# IMU.net
KiCad netlist of a schematic drawn in Altium Designer
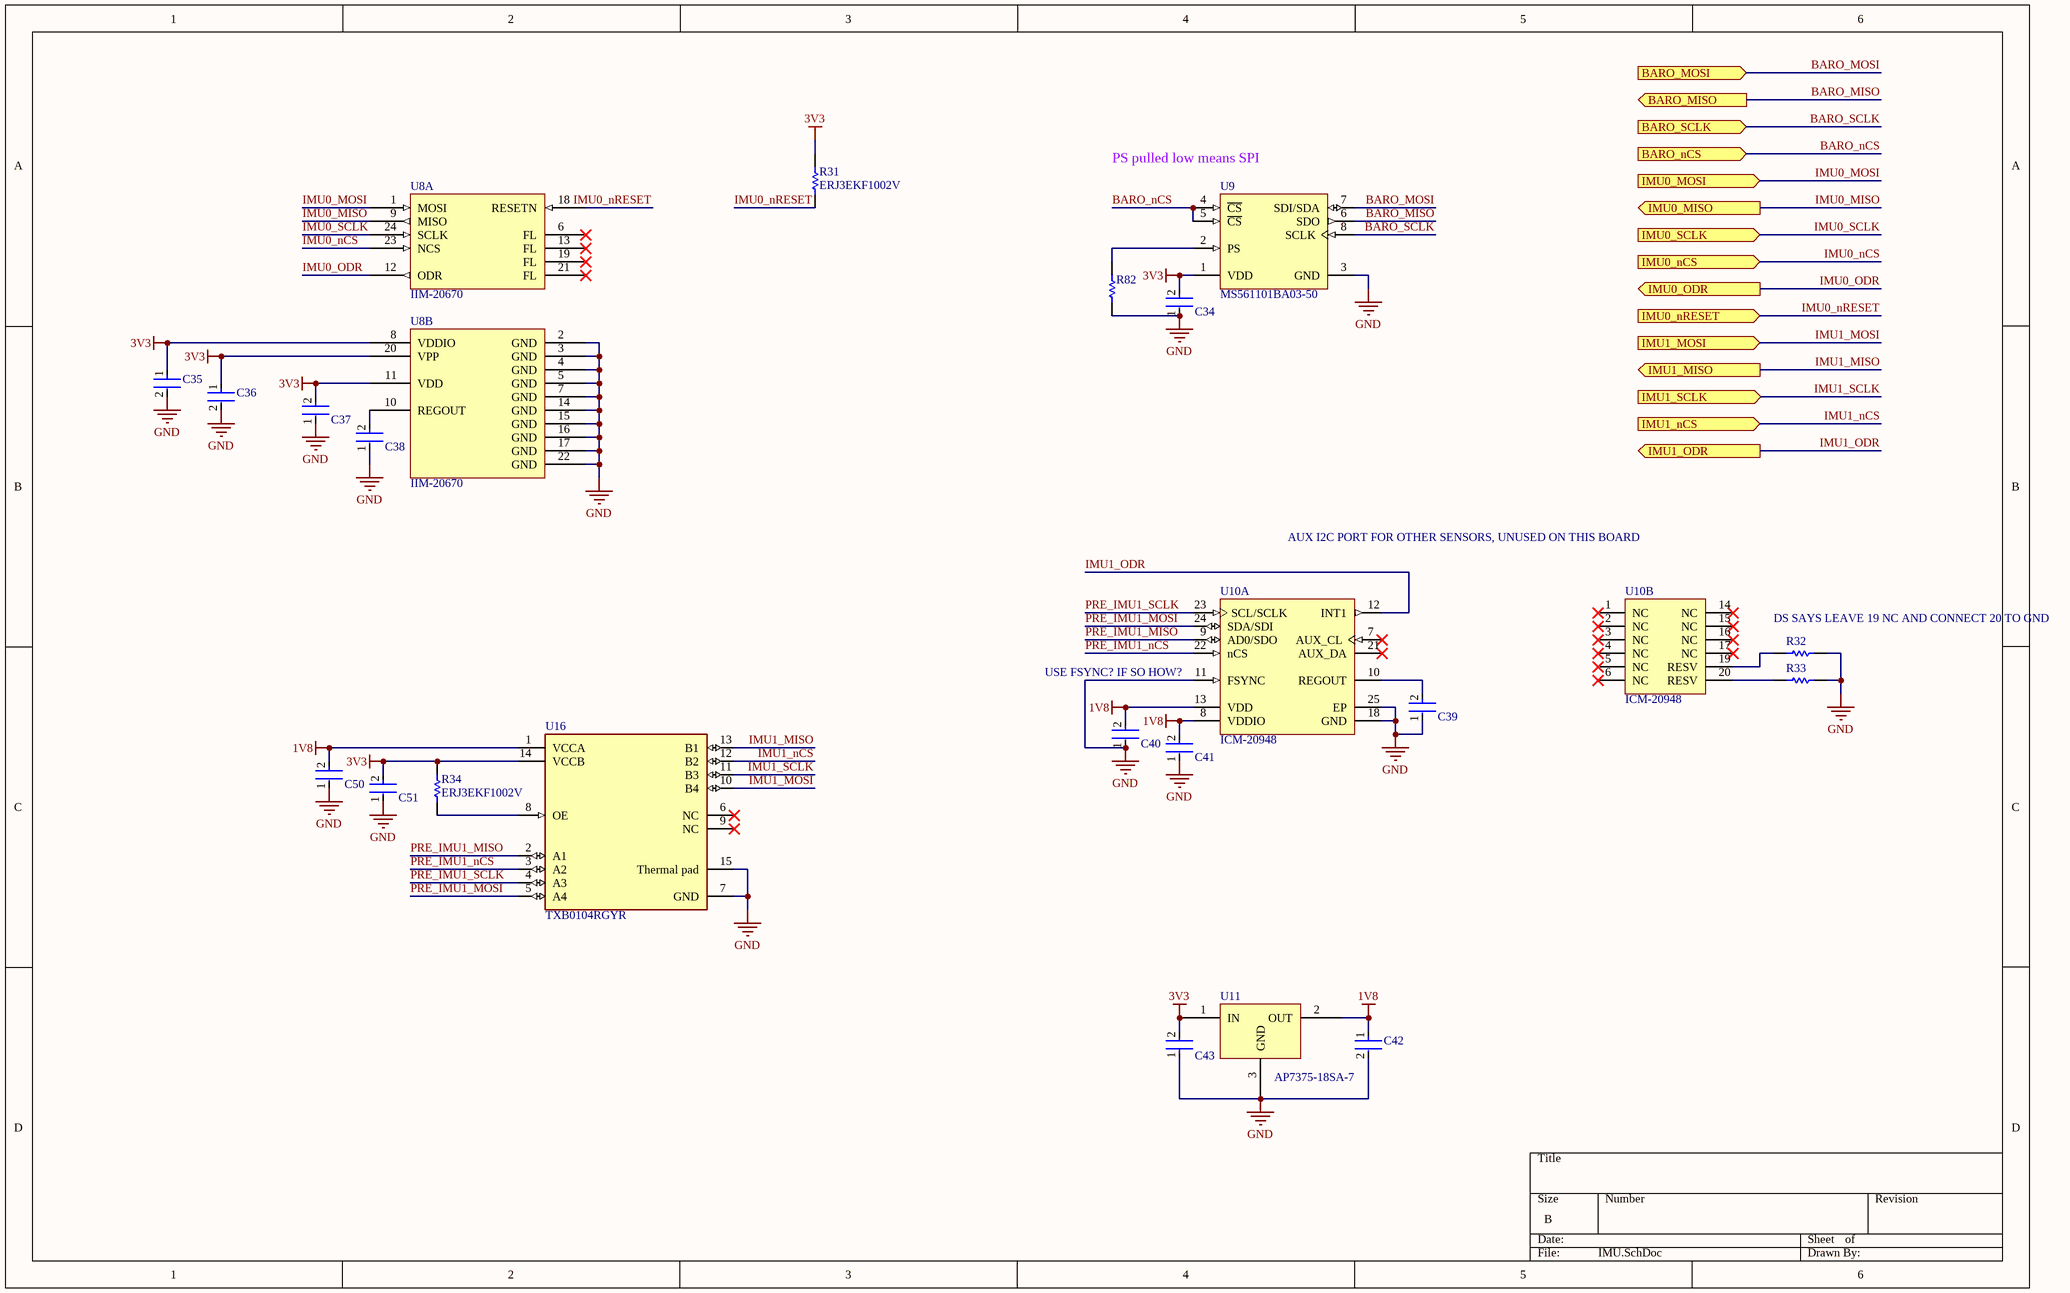
[diagram p0: IMU.SchDoc]

(export (version "E")
  (design (tool "Eeschema 10.0.6"))
  (components
    (comp (ref "C34")
      (value "GRM155R71C104KA88D")
      (footprint "FP-GRM15-MFG")
      (description "CAP CER 0.1UF 16V X7R 0402")
      (fields
        (field (name "TOLERANCE") "10%")
        (field (name "OCTOPART") "https://octopart.com/grm155r71c104ka88d-murata-196880")
      )
      (libsource (lib "Altium Content Vault") (part "236180d848d6139a670b325ea6854c9"))
    )
    (comp (ref "C35")
      (value "CC0402KPX7R7BB103")
      (footprint "FP-CC0402-MFG")
      (description "CC0402 10 nF X7R 10.00% 16 V")
      (fields
        (field (name "TOLERANCE") "0.1")
        (field (name "OCTOPART") "https://octopart.com/cc0402kpx7r7bb103-yageo-12885102")
      )
      (libsource (lib "Altium Content Vault") (part "11868f565c42a9108669ba33697ecf6"))
    )
    (comp (ref "C36")
      (value "CC0402KPX7R7BB103")
      (footprint "FP-CC0402-MFG")
      (description "CC0402 10 nF X7R 10.00% 16 V")
      (fields
        (field (name "TOLERANCE") "0.1")
        (field (name "OCTOPART") "https://octopart.com/cc0402kpx7r7bb103-yageo-12885102")
      )
      (libsource (lib "Altium Content Vault") (part "11868f565c42a9108669ba33697ecf6"))
    )
    (comp (ref "C37")
      (value "GRM155R71C104KA88D")
      (footprint "FP-GRM15-MFG")
      (description "CAP CER 0.1UF 16V X7R 0402")
      (fields
        (field (name "TOLERANCE") "10%")
        (field (name "OCTOPART") "https://octopart.com/grm155r71c104ka88d-murata-196880")
      )
      (libsource (lib "Altium Content Vault") (part "236180d848d6139a670b325ea6854c9"))
    )
    (comp (ref "C38")
      (value "GRM155R71C104KA88D")
      (footprint "FP-GRM15-MFG")
      (description "CAP CER 0.1UF 16V X7R 0402")
      (fields
        (field (name "TOLERANCE") "10%")
        (field (name "OCTOPART") "https://octopart.com/grm155r71c104ka88d-murata-196880")
      )
      (libsource (lib "Altium Content Vault") (part "236180d848d6139a670b325ea6854c9"))
    )
    (comp (ref "C39")
      (value "GRM155R71C104KA88D")
      (footprint "FP-GRM15-MFG")
      (description "CAP CER 0.1UF 16V X7R 0402")
      (fields
        (field (name "TOLERANCE") "10%")
        (field (name "OCTOPART") "https://octopart.com/grm155r71c104ka88d-murata-196880")
      )
      (libsource (lib "Altium Content Vault") (part "236180d848d6139a670b325ea6854c9"))
    )
    (comp (ref "C40")
      (value "GRM155R71C104KA88D")
      (footprint "FP-GRM15-MFG")
      (description "CAP CER 0.1UF 16V X7R 0402")
      (fields
        (field (name "TOLERANCE") "10%")
        (field (name "OCTOPART") "https://octopart.com/grm155r71c104ka88d-murata-196880")
      )
      (libsource (lib "Altium Content Vault") (part "236180d848d6139a670b325ea6854c9"))
    )
    (comp (ref "C41")
      (value "GRM155R71C104KA88D")
      (footprint "FP-GRM15-MFG")
      (description "CAP CER 0.1UF 16V X7R 0402")
      (fields
        (field (name "TOLERANCE") "10%")
        (field (name "OCTOPART") "https://octopart.com/grm155r71c104ka88d-murata-196880")
      )
      (libsource (lib "Altium Content Vault") (part "236180d848d6139a670b325ea6854c9"))
    )
    (comp (ref "C42")
      (value "CL05A106MP5NUNC")
      (footprint "FP-CL05A106MP5NUNC-MFG")
      (description "CAP CER 10UF 10V X5R 0402")
      (fields
        (field (name "OCTOPART") "https://octopart.com/cl05a106mp5nunc-samsung-22457395")
        (field (name "TOLERANCE") "20%")
      )
      (libsource (lib "Altium Content Vault") (part "b4654b650e69147ec39a6b967a45e02"))
    )
    (comp (ref "C43")
      (value "C0402C104K8PACTU")
      (footprint "FP-C0402-BB-MFG")
      (description "CAP CER 0.1UF 10V X5R 0402")
      (fields (field (name "MANUFACTURER") "Kemet") (field (name "TOLERANCE") "0.1"))
      (libsource (lib "Altium Content Vault") (part "b4654b650e69147ec39a6b967a45e02"))
    )
    (comp (ref "C50")
      (value "GRM155R71C104KA88D")
      (footprint "FP-GRM15-MFG")
      (description "CAP CER 0.1UF 16V X7R 0402")
      (fields
        (field (name "TOLERANCE") "10%")
        (field (name "OCTOPART") "https://octopart.com/grm155r71c104ka88d-murata-196880")
      )
      (libsource (lib "Altium Content Vault") (part "236180d848d6139a670b325ea6854c9"))
    )
    (comp (ref "C51")
      (value "GRM155R71C104KA88D")
      (footprint "FP-GRM15-MFG")
      (description "CAP CER 0.1UF 16V X7R 0402")
      (fields
        (field (name "TOLERANCE") "10%")
        (field (name "OCTOPART") "https://octopart.com/grm155r71c104ka88d-murata-196880")
      )
      (libsource (lib "Altium Content Vault") (part "236180d848d6139a670b325ea6854c9"))
    )
    (comp (ref "R31")
      (value "ERJ3EKF1002V")
      (footprint "RESC1609X55X30LL15T15")
      (description "Chip Resistor, 10 KOhm, +/- 1%, 0.1 W, -55 to 155 degC, 0603 (1608 Metric), RoHS, Tape and Reel")
      (fields (field (name "TOLERANCE") "1%") (field (name "MANUFACTURER") "Panasonic"))
      (libsource (lib "Altium Content Vault") (part "RES-2"))
    )
    (comp (ref "R32")
      (value "0402 JUMPER")
      (footprint "RESC1005X40X25ML05T05")
      (description "READ THE NAME")
      (libsource (lib "Space Concordia") (part "CMP-009-00206-2"))
    )
    (comp (ref "R33")
      (value "0402 JUMPER")
      (footprint "RESC1005X40X25ML05T05")
      (description "READ THE NAME")
      (libsource (lib "Space Concordia") (part "CMP-009-00206-2"))
    )
    (comp (ref "R34")
      (value "ERJ3EKF1002V")
      (footprint "RESC1609X55X30LL15T15")
      (description "Chip Resistor, 10 KOhm, +/- 1%, 0.1 W, -55 to 155 degC, 0603 (1608 Metric), RoHS, Tape and Reel")
      (fields (field (name "TOLERANCE") "1%") (field (name "MANUFACTURER") "Panasonic"))
      (libsource (lib "Altium Content Vault") (part "RES-2"))
    )
    (comp (ref "R82")
      (value "0402 JUMPER")
      (footprint "RESC1005X40X25ML05T05")
      (description "READ THE NAME")
      (libsource (lib "Space Concordia") (part "CMP-009-00206-2"))
    )
    (comp (ref "U8")
      (value "IIM-20670")
      (footprint "PQFN50P450X450X115_HS-25N")
      (description "6-axis IMU with extended temperature range and high VRE performance")
      (libsource (lib "Space Concordia") (part "IIM-20670"))
    )
    (comp (ref "U9")
      (value "MS561101BA03-50")
      (footprint "MSI-MS561101BA03-50-8_V")
      (fields (field (name "MANUFACTURER") "Measurement Specialties"))
      (libsource (lib "Altium Content Vault") (part "MSI-MS561101BA03-50-8"))
    )
    (comp (ref "U10")
      (value "ICM-20948")
      (footprint "TDK-QFN-24_L")
      (fields (field (name "MANUFACTURER") "TDK"))
      (libsource (lib "Altium Content Vault") (part "TDK-ICM-20948-QFN-24"))
    )
    (comp (ref "U11")
      (value "AP7375-18SA-7")
      (footprint "AP7375-18SA-7-Footprint-1")
      (description "Fixed Positive LDO Regulator")
      (libsource (lib "Space Concordia") (part "AP7375-18SA-7"))
    )
    (comp (ref "U16")
      (value "TXB0104RGYR")
      (footprint "FP-RGY0014A-MFG")
      (description "IC TRNSLTR BIDIRECTIONAL 14VQFN")
      (fields
        (field (name "MANUFACTURER") "Texas Instruments")
        (field (name "OCTOPART") "https://octopart.com/txb0104rgyr-texas+instruments-1485948")
      )
      (libsource (lib "Altium Content Vault") (part "00c1e25395d90d543401131e0a6fef8"))
    )
  )
  (nets
    (net (code "1") (name "/BARO_MISO") (class "Default")
      (node (ref "U9") (pin "6") (pinfunction "SDO_6") (pintype "output"))
    )
    (net (code "2") (name "/BARO_MOSI") (class "Default")
      (node (ref "U9") (pin "7") (pinfunction "SDI/SDA_7") (pintype "bidirectional"))
    )
    (net (code "3") (name "/BARO_SCLK") (class "Default")
      (node (ref "U9") (pin "8") (pinfunction "SCLK_8") (pintype "input"))
    )
    (net (code "4") (name "/BARO_nCS") (class "Default")
      (node (ref "U9") (pin "4") (pinfunction "~{CS}_4") (pintype "input"))
      (node (ref "U9") (pin "5") (pinfunction "~{CS}_5") (pintype "input"))
    )
    (net (code "5") (name "/IMU0_MISO") (class "Default")
      (node (ref "U8") (pin "9") (pinfunction "MISO_9") (pintype "output"))
    )
    (net (code "6") (name "/IMU0_MOSI") (class "Default")
      (node (ref "U8") (pin "1") (pinfunction "MOSI_1") (pintype "input"))
    )
    (net (code "7") (name "/IMU0_ODR") (class "Default")
      (node (ref "U8") (pin "12") (pinfunction "ODR_12") (pintype "output"))
    )
    (net (code "8") (name "/IMU0_SCLK") (class "Default")
      (node (ref "U8") (pin "24") (pinfunction "SCLK_24") (pintype "input"))
    )
    (net (code "9") (name "/IMU0_nCS") (class "Default")
      (node (ref "U8") (pin "23") (pinfunction "NCS_23") (pintype "input"))
    )
    (net (code "10") (name "/IMU0_nRESET") (class "Default")
      (node (ref "R31") (pin "1") (pinfunction "1_1") (pintype "passive"))
      (node (ref "U8") (pin "18") (pinfunction "RESETN_18") (pintype "input"))
    )
    (net (code "11") (name "/IMU1_MISO") (class "Default")
      (node (ref "U16") (pin "13") (pinfunction "B1_13") (pintype "bidirectional"))
    )
    (net (code "12") (name "/IMU1_MOSI") (class "Default")
      (node (ref "U16") (pin "10") (pinfunction "B4_10") (pintype "bidirectional"))
    )
    (net (code "13") (name "/IMU1_ODR") (class "Default")
      (node (ref "U10") (pin "12") (pinfunction "INT1_12") (pintype "output"))
    )
    (net (code "14") (name "/IMU1_SCLK") (class "Default")
      (node (ref "U16") (pin "11") (pinfunction "B3_11") (pintype "bidirectional"))
    )
    (net (code "15") (name "/IMU1_nCS") (class "Default")
      (node (ref "U16") (pin "12") (pinfunction "B2_12") (pintype "bidirectional"))
    )
    (net (code "16") (name "/PRE_IMU1_MISO") (class "Default")
      (node (ref "U10") (pin "9") (pinfunction "AD0/SDO_9") (pintype "bidirectional"))
      (node (ref "U16") (pin "2") (pinfunction "A1_2") (pintype "bidirectional"))
    )
    (net (code "17") (name "/PRE_IMU1_MOSI") (class "Default")
      (node (ref "U10") (pin "24") (pinfunction "SDA/SDI_24") (pintype "bidirectional"))
      (node (ref "U16") (pin "5") (pinfunction "A4_5") (pintype "bidirectional"))
    )
    (net (code "18") (name "/PRE_IMU1_SCLK") (class "Default")
      (node (ref "U10") (pin "23") (pinfunction "SCL/SCLK_23") (pintype "input"))
      (node (ref "U16") (pin "4") (pinfunction "A3_4") (pintype "bidirectional"))
    )
    (net (code "19") (name "/PRE_IMU1_nCS") (class "Default")
      (node (ref "U10") (pin "22") (pinfunction "nCS_22") (pintype "input"))
      (node (ref "U16") (pin "3") (pinfunction "A2_3") (pintype "bidirectional"))
    )
    (net (code "20") (name "1V8") (class "Default")
      (node (ref "C40") (pin "2") (pinfunction "2_2") (pintype "passive"))
      (node (ref "C41") (pin "2") (pinfunction "2_2") (pintype "passive"))
      (node (ref "C42") (pin "1") (pinfunction "1_1") (pintype "passive"))
      (node (ref "C50") (pin "2") (pinfunction "2_2") (pintype "passive"))
      (node (ref "U10") (pin "13") (pinfunction "VDD_13") (pintype "power_in"))
      (node (ref "U10") (pin "8") (pinfunction "VDDIO_8") (pintype "power_in"))
      (node (ref "U11") (pin "2") (pinfunction "OUT_2") (pintype "passive"))
      (node (ref "U16") (pin "1") (pinfunction "VCCA_1") (pintype "power_in"))
    )
    (net (code "21") (name "3V3") (class "Default")
      (node (ref "C34") (pin "2") (pinfunction "2_2") (pintype "passive"))
      (node (ref "C35") (pin "1") (pinfunction "1_1") (pintype "passive"))
      (node (ref "C36") (pin "1") (pinfunction "1_1") (pintype "passive"))
      (node (ref "C37") (pin "2") (pinfunction "2_2") (pintype "passive"))
      (node (ref "C43") (pin "2") (pinfunction "2_2") (pintype "passive"))
      (node (ref "C51") (pin "2") (pinfunction "2_2") (pintype "passive"))
      (node (ref "R31") (pin "2") (pinfunction "2_2") (pintype "passive"))
      (node (ref "R34") (pin "2") (pinfunction "2_2") (pintype "passive"))
      (node (ref "U11") (pin "1") (pinfunction "IN_1") (pintype "passive"))
      (node (ref "U16") (pin "14") (pinfunction "VCCB_14") (pintype "power_in"))
      (node (ref "U8") (pin "11") (pinfunction "VDD_11") (pintype "power_in"))
      (node (ref "U8") (pin "20") (pinfunction "VPP_20") (pintype "power_in"))
      (node (ref "U8") (pin "8") (pinfunction "VDDIO_8") (pintype "power_in"))
      (node (ref "U9") (pin "1") (pinfunction "VDD_1") (pintype "power_in"))
    )
    (net (code "22") (name "GND") (class "Default")
      (node (ref "C34") (pin "1") (pinfunction "1_1") (pintype "passive"))
      (node (ref "C35") (pin "2") (pinfunction "2_2") (pintype "passive"))
      (node (ref "C36") (pin "2") (pinfunction "2_2") (pintype "passive"))
      (node (ref "C37") (pin "1") (pinfunction "1_1") (pintype "passive"))
      (node (ref "C38") (pin "1") (pinfunction "1_1") (pintype "passive"))
      (node (ref "C39") (pin "1") (pinfunction "1_1") (pintype "passive"))
      (node (ref "C40") (pin "1") (pinfunction "1_1") (pintype "passive"))
      (node (ref "C41") (pin "1") (pinfunction "1_1") (pintype "passive"))
      (node (ref "C42") (pin "2") (pinfunction "2_2") (pintype "passive"))
      (node (ref "C43") (pin "1") (pinfunction "1_1") (pintype "passive"))
      (node (ref "C50") (pin "1") (pinfunction "1_1") (pintype "passive"))
      (node (ref "C51") (pin "1") (pinfunction "1_1") (pintype "passive"))
      (node (ref "R32") (pin "2") (pinfunction "2_2") (pintype "passive"))
      (node (ref "R33") (pin "2") (pinfunction "2_2") (pintype "passive"))
      (node (ref "R82") (pin "1") (pinfunction "1_1") (pintype "passive"))
      (node (ref "U10") (pin "11") (pinfunction "FSYNC_11") (pintype "input"))
      (node (ref "U10") (pin "18") (pinfunction "GND_18") (pintype "power_in"))
      (node (ref "U10") (pin "25") (pinfunction "EP_25") (pintype "passive"))
      (node (ref "U11") (pin "3") (pinfunction "GND_3") (pintype "passive"))
      (node (ref "U16") (pin "15") (pinfunction "Thermal_pad_15") (pintype "power_in"))
      (node (ref "U16") (pin "7") (pinfunction "GND_7") (pintype "power_in"))
      (node (ref "U8") (pin "14") (pinfunction "GND_14") (pintype "power_in"))
      (node (ref "U8") (pin "15") (pinfunction "GND_15") (pintype "power_in"))
      (node (ref "U8") (pin "16") (pinfunction "GND_16") (pintype "power_in"))
      (node (ref "U8") (pin "17") (pinfunction "GND_17") (pintype "power_in"))
      (node (ref "U8") (pin "2") (pinfunction "GND_2") (pintype "power_in"))
      (node (ref "U8") (pin "22") (pinfunction "GND_22") (pintype "power_in"))
      (node (ref "U8") (pin "3") (pinfunction "GND_3") (pintype "power_in"))
      (node (ref "U8") (pin "4") (pinfunction "GND_4") (pintype "power_in"))
      (node (ref "U8") (pin "5") (pinfunction "GND_5") (pintype "power_in"))
      (node (ref "U8") (pin "7") (pinfunction "GND_7") (pintype "power_in"))
      (node (ref "U9") (pin "3") (pinfunction "GND_3") (pintype "power_in"))
    )
    (net (code "23") (name "Net-(R32-Pad1)") (class "Default")
      (node (ref "R32") (pin "1") (pinfunction "1_1") (pintype "passive"))
      (node (ref "U10") (pin "19") (pinfunction "RESV_19") (pintype "passive"))
    )
    (net (code "24") (name "Net-(R33-Pad1)") (class "Default")
      (node (ref "R33") (pin "1") (pinfunction "1_1") (pintype "passive"))
      (node (ref "U10") (pin "20") (pinfunction "RESV_20") (pintype "passive"))
    )
    (net (code "25") (name "Net-(U8B-REGOUT)") (class "Default")
      (node (ref "C38") (pin "2") (pinfunction "2_2") (pintype "passive"))
      (node (ref "U8") (pin "10") (pinfunction "REGOUT_10") (pintype "passive"))
    )
    (net (code "26") (name "Net-(U9-PS)") (class "Default")
      (node (ref "R82") (pin "2") (pinfunction "2_2") (pintype "passive"))
      (node (ref "U9") (pin "2") (pinfunction "PS_2") (pintype "input"))
    )
    (net (code "27") (name "Net-(U10A-REGOUT)") (class "Default")
      (node (ref "C39") (pin "2") (pinfunction "2_2") (pintype "passive"))
      (node (ref "U10") (pin "10") (pinfunction "REGOUT_10") (pintype "passive"))
    )
    (net (code "28") (name "Net-(U16-OE)") (class "Default")
      (node (ref "R34") (pin "1") (pinfunction "1_1") (pintype "passive"))
      (node (ref "U16") (pin "8") (pinfunction "OE_8") (pintype "input"))
    )
    (net (code "29") (name "unconnected-(U8A-FL-Pad6)") (class "Default")
      (node (ref "U8") (pin "6") (pinfunction "FL_6") (pintype "passive+no_connect"))
    )
    (net (code "30") (name "unconnected-(U8A-FL-Pad13)") (class "Default")
      (node (ref "U8") (pin "13") (pinfunction "FL_13") (pintype "passive+no_connect"))
    )
    (net (code "31") (name "unconnected-(U8A-FL-Pad19)") (class "Default")
      (node (ref "U8") (pin "19") (pinfunction "FL_19") (pintype "passive+no_connect"))
    )
    (net (code "32") (name "unconnected-(U8A-FL-Pad21)") (class "Default")
      (node (ref "U8") (pin "21") (pinfunction "FL_21") (pintype "passive+no_connect"))
    )
    (net (code "33") (name "unconnected-(U10A-AUX_CL-Pad7)") (class "Default")
      (node (ref "U10") (pin "7") (pinfunction "AUX_CL_7") (pintype "input+no_connect"))
    )
    (net (code "34") (name "unconnected-(U10A-AUX_DA-Pad21)") (class "Default")
      (node (ref "U10") (pin "21") (pinfunction "AUX_DA_21") (pintype "passive+no_connect"))
    )
    (net (code "35") (name "unconnected-(U10B-NC-Pad1)") (class "Default")
      (node (ref "U10") (pin "1") (pinfunction "NC_1") (pintype "passive+no_connect"))
    )
    (net (code "36") (name "unconnected-(U10B-NC-Pad2)") (class "Default")
      (node (ref "U10") (pin "2") (pinfunction "NC_2") (pintype "passive+no_connect"))
    )
    (net (code "37") (name "unconnected-(U10B-NC-Pad3)") (class "Default")
      (node (ref "U10") (pin "3") (pinfunction "NC_3") (pintype "passive+no_connect"))
    )
    (net (code "38") (name "unconnected-(U10B-NC-Pad4)") (class "Default")
      (node (ref "U10") (pin "4") (pinfunction "NC_4") (pintype "passive+no_connect"))
    )
    (net (code "39") (name "unconnected-(U10B-NC-Pad5)") (class "Default")
      (node (ref "U10") (pin "5") (pinfunction "NC_5") (pintype "passive+no_connect"))
    )
    (net (code "40") (name "unconnected-(U10B-NC-Pad6)") (class "Default")
      (node (ref "U10") (pin "6") (pinfunction "NC_6") (pintype "passive+no_connect"))
    )
    (net (code "41") (name "unconnected-(U10B-NC-Pad14)") (class "Default")
      (node (ref "U10") (pin "14") (pinfunction "NC_14") (pintype "passive+no_connect"))
    )
    (net (code "42") (name "unconnected-(U10B-NC-Pad15)") (class "Default")
      (node (ref "U10") (pin "15") (pinfunction "NC_15") (pintype "passive+no_connect"))
    )
    (net (code "43") (name "unconnected-(U10B-NC-Pad16)") (class "Default")
      (node (ref "U10") (pin "16") (pinfunction "NC_16") (pintype "passive+no_connect"))
    )
    (net (code "44") (name "unconnected-(U10B-NC-Pad17)") (class "Default")
      (node (ref "U10") (pin "17") (pinfunction "NC_17") (pintype "passive+no_connect"))
    )
    (net (code "45") (name "unconnected-(U16-NC-Pad6)") (class "Default")
      (node (ref "U16") (pin "6") (pinfunction "NC_6") (pintype "passive+no_connect"))
    )
    (net (code "46") (name "unconnected-(U16-NC-Pad9)") (class "Default")
      (node (ref "U16") (pin "9") (pinfunction "NC_9") (pintype "passive+no_connect"))
    )
  )
)
